# STM32F103C8T6___V1_0___AD.net
KiCad netlist of a schematic drawn in Altium Designer
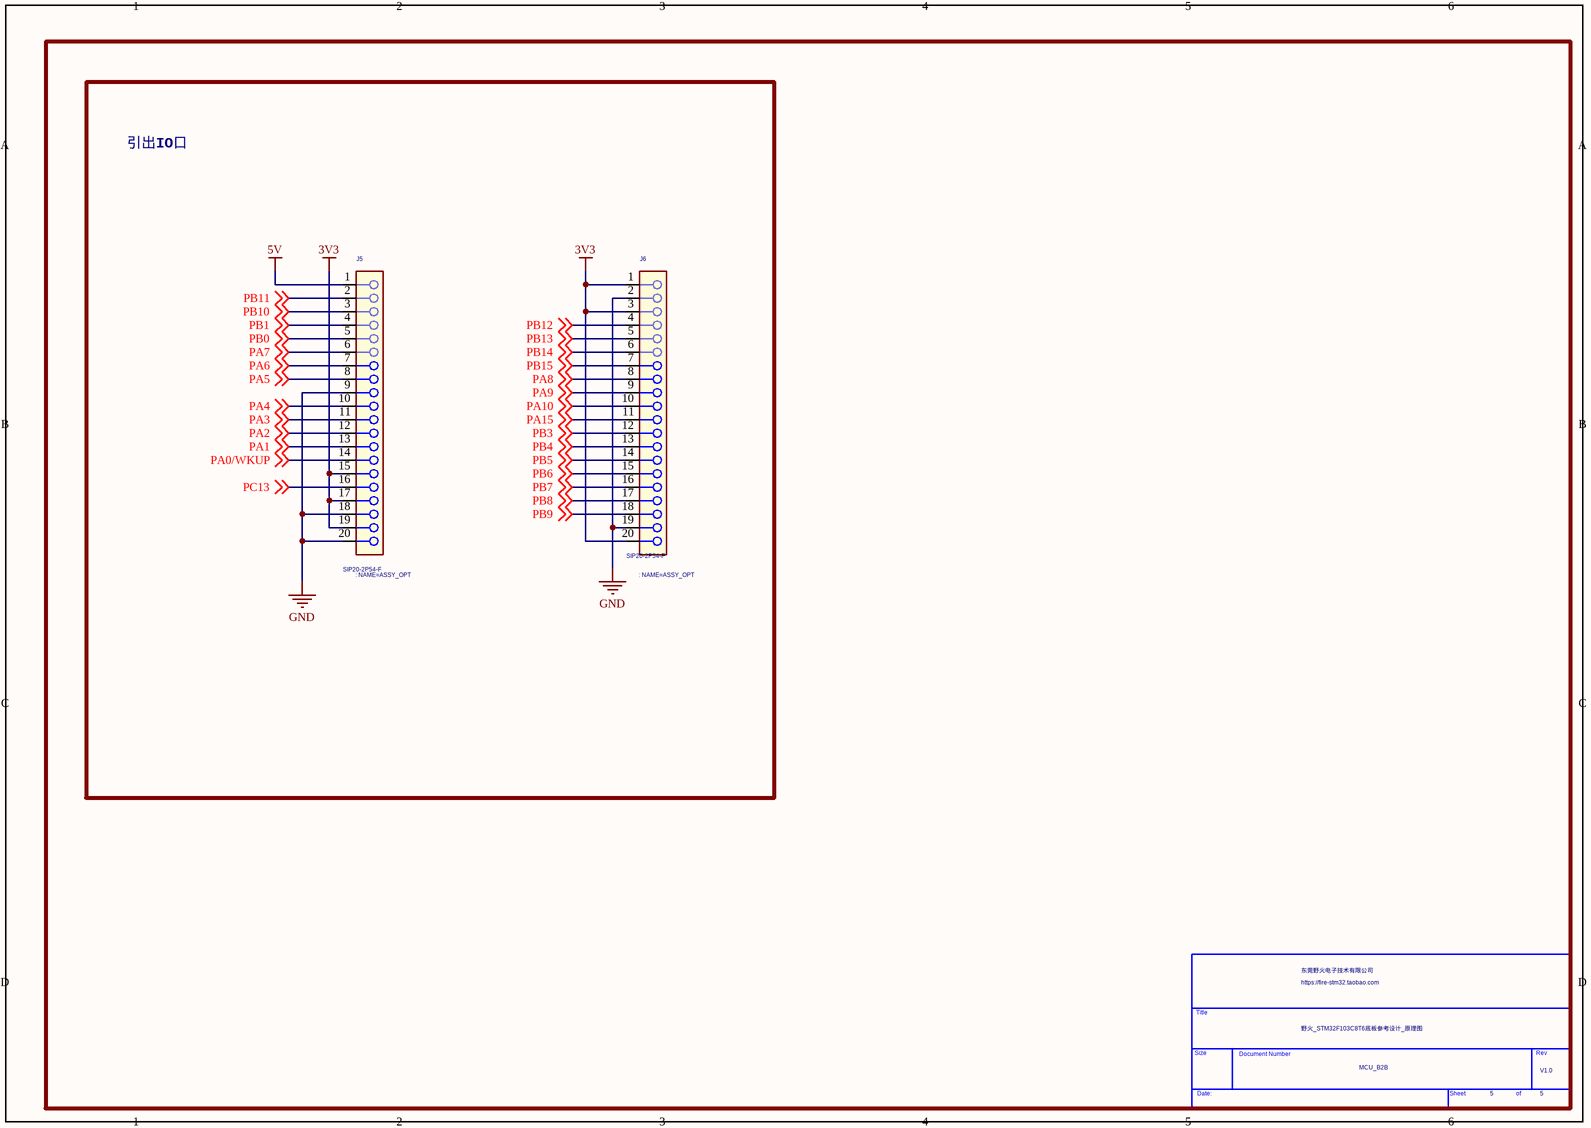
[diagram p0: 野火_STM32F103C8T6_核心板_V1.0_底板原理图参考设计_AD格式.SchDoc]

(export (version "E")
  (design (tool "Eeschema 10.0.6"))
  (components
    (comp (ref "*")
      (value "TitleBlock_YHSCH")
      (fields
        (field (name "DOC") "MCU_B2B")
        (field (name "REVCODE") "V1.0")
        (field (name "TITLE") "野火_STM32F103C8T6底板参考设计_原理图")
        (field (name "ORGNAME") "东莞野火电子技术有限公司")
        (field (name "ORGADDR1") "https://fire-stm32.taobao.com")
        (field (name "PAGE NUMBER") "5")
        (field (name "PAGE COUNT") "5")
      )
      (libsource (lib "*") (part "TitleBlock_YHSCH"))
    )
    (comp (ref "J5")
      (value "SIP20-2P54-F")
      (description "CON 1X6 SKT TH 100MIL SP 344H AU 118L")
      (fields (field (name "ALTIUM_UNNAMED_1") "NAME=ASSY_OPT"))
      (libsource (lib "*") (part "CONN_HDR_1"))
    )
    (comp (ref "J6")
      (value "SIP20-2P54-F")
      (description "CON 1X6 SKT TH 100MIL SP 344H AU 118L")
      (fields (field (name "ALTIUM_UNNAMED_1") "NAME=ASSY_OPT"))
      (libsource (lib "*") (part "CONN_HDR_1"))
    )
  )
  (nets
    (net (code "1") (name "3V3") (class "Default")
      (node (ref "J5") (pin "15") (pinfunction "15_15") (pintype "passive"))
      (node (ref "J5") (pin "17") (pinfunction "17_17") (pintype "passive"))
      (node (ref "J5") (pin "19") (pinfunction "19_19") (pintype "passive"))
      (node (ref "J6") (pin "1") (pinfunction "1_1") (pintype "passive"))
      (node (ref "J6") (pin "20") (pinfunction "20_20") (pintype "passive"))
      (node (ref "J6") (pin "3") (pinfunction "3_3") (pintype "passive"))
    )
    (net (code "2") (name "5V") (class "Default")
      (node (ref "J5") (pin "1") (pinfunction "1_1") (pintype "passive"))
    )
    (net (code "3") (name "GND") (class "Default")
      (node (ref "J5") (pin "18") (pinfunction "18_18") (pintype "passive"))
      (node (ref "J5") (pin "20") (pinfunction "20_20") (pintype "passive"))
      (node (ref "J5") (pin "9") (pinfunction "9_9") (pintype "passive"))
      (node (ref "J6") (pin "19") (pinfunction "19_19") (pintype "passive"))
      (node (ref "J6") (pin "2") (pinfunction "2_2") (pintype "passive"))
    )
    (net (code "4") (name "PA0{slash}WKUP") (class "Default")
      (node (ref "J5") (pin "14") (pinfunction "14_14") (pintype "passive"))
    )
    (net (code "5") (name "PA1") (class "Default")
      (node (ref "J5") (pin "13") (pinfunction "13_13") (pintype "passive"))
    )
    (net (code "6") (name "PA2") (class "Default")
      (node (ref "J5") (pin "12") (pinfunction "12_12") (pintype "passive"))
    )
    (net (code "7") (name "PA3") (class "Default")
      (node (ref "J5") (pin "11") (pinfunction "11_11") (pintype "passive"))
    )
    (net (code "8") (name "PA4") (class "Default")
      (node (ref "J5") (pin "10") (pinfunction "10_10") (pintype "passive"))
    )
    (net (code "9") (name "PA5") (class "Default")
      (node (ref "J5") (pin "8") (pinfunction "8_8") (pintype "passive"))
    )
    (net (code "10") (name "PA6") (class "Default")
      (node (ref "J5") (pin "7") (pinfunction "7_7") (pintype "passive"))
    )
    (net (code "11") (name "PA7") (class "Default")
      (node (ref "J5") (pin "6") (pinfunction "6_6") (pintype "passive"))
    )
    (net (code "12") (name "PA8") (class "Default")
      (node (ref "J6") (pin "8") (pinfunction "8_8") (pintype "passive"))
    )
    (net (code "13") (name "PA9") (class "Default")
      (node (ref "J6") (pin "9") (pinfunction "9_9") (pintype "passive"))
    )
    (net (code "14") (name "PA10") (class "Default")
      (node (ref "J6") (pin "10") (pinfunction "10_10") (pintype "passive"))
    )
    (net (code "15") (name "PA15") (class "Default")
      (node (ref "J6") (pin "11") (pinfunction "11_11") (pintype "passive"))
    )
    (net (code "16") (name "PB0") (class "Default")
      (node (ref "J5") (pin "5") (pinfunction "5_5") (pintype "passive"))
    )
    (net (code "17") (name "PB1") (class "Default")
      (node (ref "J5") (pin "4") (pinfunction "4_4") (pintype "passive"))
    )
    (net (code "18") (name "PB3") (class "Default")
      (node (ref "J6") (pin "12") (pinfunction "12_12") (pintype "passive"))
    )
    (net (code "19") (name "PB4") (class "Default")
      (node (ref "J6") (pin "13") (pinfunction "13_13") (pintype "passive"))
    )
    (net (code "20") (name "PB5") (class "Default")
      (node (ref "J6") (pin "14") (pinfunction "14_14") (pintype "passive"))
    )
    (net (code "21") (name "PB6") (class "Default")
      (node (ref "J6") (pin "15") (pinfunction "15_15") (pintype "passive"))
    )
    (net (code "22") (name "PB7") (class "Default")
      (node (ref "J6") (pin "16") (pinfunction "16_16") (pintype "passive"))
    )
    (net (code "23") (name "PB8") (class "Default")
      (node (ref "J6") (pin "17") (pinfunction "17_17") (pintype "passive"))
    )
    (net (code "24") (name "PB9") (class "Default")
      (node (ref "J6") (pin "18") (pinfunction "18_18") (pintype "passive"))
    )
    (net (code "25") (name "PB10") (class "Default")
      (node (ref "J5") (pin "3") (pinfunction "3_3") (pintype "passive"))
    )
    (net (code "26") (name "PB11") (class "Default")
      (node (ref "J5") (pin "2") (pinfunction "2_2") (pintype "passive"))
    )
    (net (code "27") (name "PB12") (class "Default")
      (node (ref "J6") (pin "4") (pinfunction "4_4") (pintype "passive"))
    )
    (net (code "28") (name "PB13") (class "Default")
      (node (ref "J6") (pin "5") (pinfunction "5_5") (pintype "passive"))
    )
    (net (code "29") (name "PB14") (class "Default")
      (node (ref "J6") (pin "6") (pinfunction "6_6") (pintype "passive"))
    )
    (net (code "30") (name "PB15") (class "Default")
      (node (ref "J6") (pin "7") (pinfunction "7_7") (pintype "passive"))
    )
    (net (code "31") (name "PC13") (class "Default")
      (node (ref "J5") (pin "16") (pinfunction "16_16") (pintype "passive"))
    )
  )
)
